# BalEv_ADC_v1_0.net
KiCad netlist of a schematic drawn in Altium Designer
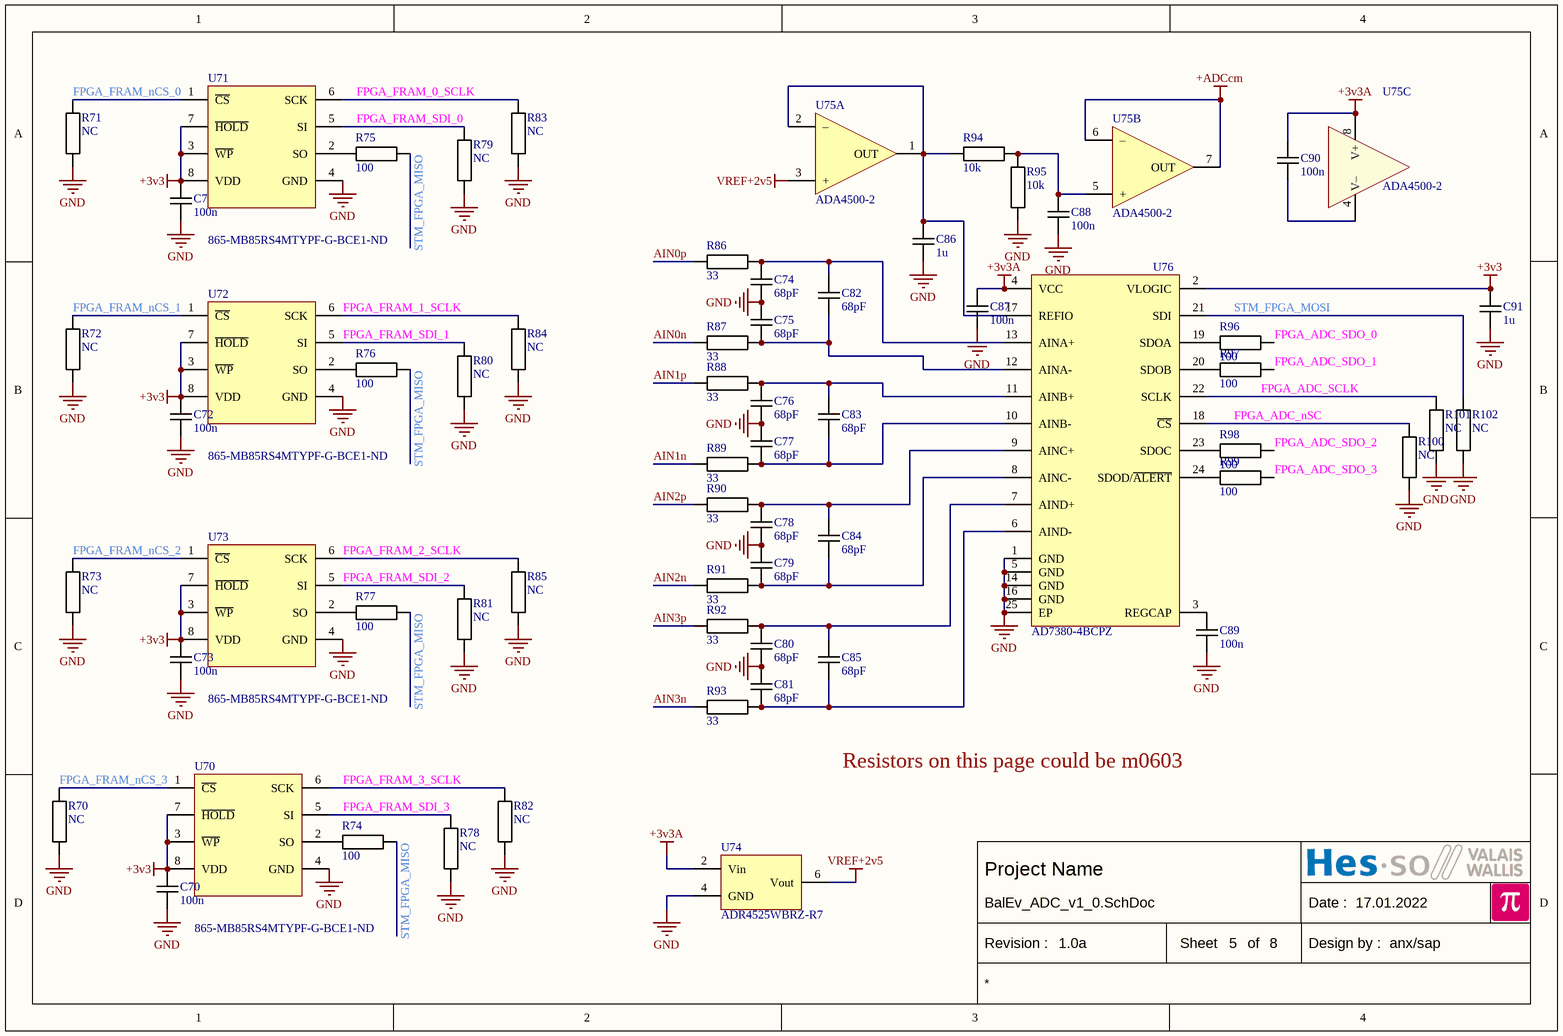
[diagram p0: BalEv_ADC_v1_0.SchDoc]

(export (version "E")
  (design (tool "Eeschema 10.0.6"))
  (components
    (comp (ref "C70")
      (value "100n")
      (footprint "CAPACITOR 1005 REFLOW")
      (description "Capacitor")
      (libsource (lib "Capacitor") (part "Capacitor"))
    )
    (comp (ref "C71")
      (value "100n")
      (footprint "CAPACITOR 1005 REFLOW")
      (description "Capacitor")
      (libsource (lib "Capacitor") (part "Capacitor"))
    )
    (comp (ref "C72")
      (value "100n")
      (footprint "CAPACITOR 1005 REFLOW")
      (description "Capacitor")
      (libsource (lib "Capacitor") (part "Capacitor"))
    )
    (comp (ref "C73")
      (value "100n")
      (footprint "CAPACITOR 1005 REFLOW")
      (description "Capacitor")
      (libsource (lib "Capacitor") (part "Capacitor"))
    )
    (comp (ref "C74")
      (value "68pF")
      (footprint "CAPACITOR 1005 REFLOW")
      (description "Capacitor")
      (libsource (lib "Capacitor") (part "Capacitor"))
    )
    (comp (ref "C75")
      (value "68pF")
      (footprint "CAPACITOR 1005 REFLOW")
      (description "Capacitor")
      (libsource (lib "Capacitor") (part "Capacitor"))
    )
    (comp (ref "C76")
      (value "68pF")
      (footprint "CAPACITOR 1005 REFLOW")
      (description "Capacitor")
      (libsource (lib "Capacitor") (part "Capacitor"))
    )
    (comp (ref "C77")
      (value "68pF")
      (footprint "CAPACITOR 1005 REFLOW")
      (description "Capacitor")
      (libsource (lib "Capacitor") (part "Capacitor"))
    )
    (comp (ref "C78")
      (value "68pF")
      (footprint "CAPACITOR 1005 REFLOW")
      (description "Capacitor")
      (libsource (lib "Capacitor") (part "Capacitor"))
    )
    (comp (ref "C79")
      (value "68pF")
      (footprint "CAPACITOR 1005 REFLOW")
      (description "Capacitor")
      (libsource (lib "Capacitor") (part "Capacitor"))
    )
    (comp (ref "C80")
      (value "68pF")
      (footprint "CAPACITOR 1005 REFLOW")
      (description "Capacitor")
      (libsource (lib "Capacitor") (part "Capacitor"))
    )
    (comp (ref "C81")
      (value "68pF")
      (footprint "CAPACITOR 1005 REFLOW")
      (description "Capacitor")
      (libsource (lib "Capacitor") (part "Capacitor"))
    )
    (comp (ref "C82")
      (value "68pF")
      (footprint "CAPACITOR 1005 REFLOW")
      (description "Capacitor")
      (libsource (lib "Capacitor") (part "Capacitor"))
    )
    (comp (ref "C83")
      (value "68pF")
      (footprint "CAPACITOR 1005 REFLOW")
      (description "Capacitor")
      (libsource (lib "Capacitor") (part "Capacitor"))
    )
    (comp (ref "C84")
      (value "68pF")
      (footprint "CAPACITOR 1005 REFLOW")
      (description "Capacitor")
      (libsource (lib "Capacitor") (part "Capacitor"))
    )
    (comp (ref "C85")
      (value "68pF")
      (footprint "CAPACITOR 1005 REFLOW")
      (description "Capacitor")
      (libsource (lib "Capacitor") (part "Capacitor"))
    )
    (comp (ref "C86")
      (value "1u")
      (footprint "CAPACITOR 1005 REFLOW")
      (description "Capacitor")
      (libsource (lib "Capacitor") (part "Capacitor"))
    )
    (comp (ref "C87")
      (value "100n")
      (footprint "CAPACITOR 1005 REFLOW")
      (description "Capacitor")
      (libsource (lib "Capacitor") (part "Capacitor"))
    )
    (comp (ref "C88")
      (value "100n")
      (footprint "CAPACITOR 1005 REFLOW")
      (description "Capacitor")
      (libsource (lib "Capacitor") (part "Capacitor"))
    )
    (comp (ref "C89")
      (value "100n")
      (footprint "CAPACITOR 1005 REFLOW")
      (description "Capacitor")
      (libsource (lib "Capacitor") (part "Capacitor"))
    )
    (comp (ref "C90")
      (value "100n")
      (footprint "CAPACITOR 1005 REFLOW")
      (description "Capacitor")
      (libsource (lib "Capacitor") (part "Capacitor"))
    )
    (comp (ref "C91")
      (value "1u")
      (footprint "CAPACITOR 1005 REFLOW")
      (description "Capacitor")
      (libsource (lib "Capacitor") (part "Capacitor"))
    )
    (comp (ref "R70")
      (value "NC")
      (footprint "RESISTOR 1005 REFLOW")
      (description "Resistor")
      (libsource (lib "Resistor") (part "Resistor"))
    )
    (comp (ref "R71")
      (value "NC")
      (footprint "RESISTOR 1005 REFLOW")
      (description "Resistor")
      (libsource (lib "Resistor") (part "Resistor"))
    )
    (comp (ref "R72")
      (value "NC")
      (footprint "RESISTOR 1005 REFLOW")
      (description "Resistor")
      (libsource (lib "Resistor") (part "Resistor"))
    )
    (comp (ref "R73")
      (value "NC")
      (footprint "RESISTOR 1005 REFLOW")
      (description "Resistor")
      (libsource (lib "Resistor") (part "Resistor"))
    )
    (comp (ref "R74")
      (value "100")
      (footprint "RESISTOR 1005 REFLOW")
      (description "Resistor")
      (libsource (lib "Resistor") (part "Resistor"))
    )
    (comp (ref "R75")
      (value "100")
      (footprint "RESISTOR 1005 REFLOW")
      (description "Resistor")
      (libsource (lib "Resistor") (part "Resistor"))
    )
    (comp (ref "R76")
      (value "100")
      (footprint "RESISTOR 1005 REFLOW")
      (description "Resistor")
      (libsource (lib "Resistor") (part "Resistor"))
    )
    (comp (ref "R77")
      (value "100")
      (footprint "RESISTOR 1005 REFLOW")
      (description "Resistor")
      (libsource (lib "Resistor") (part "Resistor"))
    )
    (comp (ref "R78")
      (value "NC")
      (footprint "RESISTOR 1005 REFLOW")
      (description "Resistor")
      (libsource (lib "Resistor") (part "Resistor"))
    )
    (comp (ref "R79")
      (value "NC")
      (footprint "RESISTOR 1005 REFLOW")
      (description "Resistor")
      (libsource (lib "Resistor") (part "Resistor"))
    )
    (comp (ref "R80")
      (value "NC")
      (footprint "RESISTOR 1005 REFLOW")
      (description "Resistor")
      (libsource (lib "Resistor") (part "Resistor"))
    )
    (comp (ref "R81")
      (value "NC")
      (footprint "RESISTOR 1005 REFLOW")
      (description "Resistor")
      (libsource (lib "Resistor") (part "Resistor"))
    )
    (comp (ref "R82")
      (value "NC")
      (footprint "RESISTOR 1005 REFLOW")
      (description "Resistor")
      (libsource (lib "Resistor") (part "Resistor"))
    )
    (comp (ref "R83")
      (value "NC")
      (footprint "RESISTOR 1005 REFLOW")
      (description "Resistor")
      (libsource (lib "Resistor") (part "Resistor"))
    )
    (comp (ref "R84")
      (value "NC")
      (footprint "RESISTOR 1005 REFLOW")
      (description "Resistor")
      (libsource (lib "Resistor") (part "Resistor"))
    )
    (comp (ref "R85")
      (value "NC")
      (footprint "RESISTOR 1005 REFLOW")
      (description "Resistor")
      (libsource (lib "Resistor") (part "Resistor"))
    )
    (comp (ref "R86")
      (value "33")
      (footprint "RESISTOR 1005 REFLOW")
      (description "Resistor")
      (libsource (lib "Resistor") (part "Resistor"))
    )
    (comp (ref "R87")
      (value "33")
      (footprint "RESISTOR 1005 REFLOW")
      (description "Resistor")
      (libsource (lib "Resistor") (part "Resistor"))
    )
    (comp (ref "R88")
      (value "33")
      (footprint "RESISTOR 1005 REFLOW")
      (description "Resistor")
      (libsource (lib "Resistor") (part "Resistor"))
    )
    (comp (ref "R89")
      (value "33")
      (footprint "RESISTOR 1005 REFLOW")
      (description "Resistor")
      (libsource (lib "Resistor") (part "Resistor"))
    )
    (comp (ref "R90")
      (value "33")
      (footprint "RESISTOR 1005 REFLOW")
      (description "Resistor")
      (libsource (lib "Resistor") (part "Resistor"))
    )
    (comp (ref "R91")
      (value "33")
      (footprint "RESISTOR 1005 REFLOW")
      (description "Resistor")
      (libsource (lib "Resistor") (part "Resistor"))
    )
    (comp (ref "R92")
      (value "33")
      (footprint "RESISTOR 1005 REFLOW")
      (description "Resistor")
      (libsource (lib "Resistor") (part "Resistor"))
    )
    (comp (ref "R93")
      (value "33")
      (footprint "RESISTOR 1005 REFLOW")
      (description "Resistor")
      (libsource (lib "Resistor") (part "Resistor"))
    )
    (comp (ref "R94")
      (value "10k")
      (footprint "RESISTOR 1005 REFLOW")
      (description "Resistor 0.01% (RNCF0603TKW10K0)")
      (libsource (lib "Resistor") (part "Resistor"))
    )
    (comp (ref "R95")
      (value "10k")
      (footprint "RESISTOR 1005 REFLOW")
      (description "Resistor 0.01% (RNCF0603TKW10K0)")
      (libsource (lib "Resistor") (part "Resistor"))
    )
    (comp (ref "R96")
      (value "100")
      (footprint "RESISTOR 1005 REFLOW")
      (description "Resistor")
      (libsource (lib "Resistor") (part "Resistor"))
    )
    (comp (ref "R97")
      (value "100")
      (footprint "RESISTOR 1005 REFLOW")
      (description "Resistor")
      (libsource (lib "Resistor") (part "Resistor"))
    )
    (comp (ref "R98")
      (value "100")
      (footprint "RESISTOR 1005 REFLOW")
      (description "Resistor")
      (libsource (lib "Resistor") (part "Resistor"))
    )
    (comp (ref "R99")
      (value "100")
      (footprint "RESISTOR 1005 REFLOW")
      (description "Resistor")
      (libsource (lib "Resistor") (part "Resistor"))
    )
    (comp (ref "R100")
      (value "NC")
      (footprint "RESISTOR 1005 REFLOW")
      (description "Resistor")
      (libsource (lib "Resistor") (part "Resistor"))
    )
    (comp (ref "R101")
      (value "NC")
      (footprint "RESISTOR 1005 REFLOW")
      (description "Resistor")
      (libsource (lib "Resistor") (part "Resistor"))
    )
    (comp (ref "R102")
      (value "NC")
      (footprint "RESISTOR 1005 REFLOW")
      (description "Resistor")
      (libsource (lib "Resistor") (part "Resistor"))
    )
    (comp (ref "U70")
      (value "865-MB85RS4MTYPF-G-BCE1-ND")
      (footprint "SO8W P1.27 C5.0X5.0 H2.0")
      (description "2-Mbit (256 K × 8) Serial (SPI) F-RAM")
      (libsource (lib "Memory") (part "FM25V20A-G"))
    )
    (comp (ref "U71")
      (value "865-MB85RS4MTYPF-G-BCE1-ND")
      (footprint "SO8W P1.27 C5.0X5.0 H2.0")
      (description "2-Mbit (256 K × 8) Serial (SPI) F-RAM")
      (libsource (lib "Memory") (part "FM25V20A-G"))
    )
    (comp (ref "U72")
      (value "865-MB85RS4MTYPF-G-BCE1-ND")
      (footprint "SO8W P1.27 C5.0X5.0 H2.0")
      (description "2-Mbit (256 K × 8) Serial (SPI) F-RAM")
      (libsource (lib "Memory") (part "FM25V20A-G"))
    )
    (comp (ref "U73")
      (value "865-MB85RS4MTYPF-G-BCE1-ND")
      (footprint "SO8W P1.27 C5.0X5.0 H2.0")
      (description "2-Mbit (256 K × 8) Serial (SPI) F-RAM")
      (libsource (lib "Memory") (part "FM25V20A-G"))
    )
    (comp (ref "U74")
      (value "ADR4525WBRZ-R7")
      (footprint "SO8 P1.27 C4.0X5.0 H1.75")
      (description "Ultralow Noise, High Accuracy Voltage References")
      (libsource (lib "Regulator") (part "ADR45___RZ (SOIC8)"))
    )
    (comp (ref "U75")
      (value "ADA4500-2")
      (footprint "MSOP8 P0.65 C3.0X3.0 H1.1")
      (description "Generic dual OPA 8 pins")
      (libsource (lib "Amplifier") (part "OPA DUAL"))
    )
    (comp (ref "U76")
      (value "AD7380-4BCPZ")
      (footprint "QFN24 P0.5 T0.5x0.5 C4.0x4.0 H0.6")
      (description "Differential Input, Quad, External Reference \r\nSimultaneous Sampling, 16-Bit, SAR ADC")
      (libsource (lib "Converter") (part "AD7380-4BCPZ"))
    )
  )
  (nets
    (net (code "1") (name "+3v3") (class "Default")
      (node (ref "C70") (pin "2") (pinfunction "2_2") (pintype "passive"))
      (node (ref "C71") (pin "2") (pinfunction "2_2") (pintype "passive"))
      (node (ref "C72") (pin "2") (pinfunction "2_2") (pintype "passive"))
      (node (ref "C73") (pin "2") (pinfunction "2_2") (pintype "passive"))
      (node (ref "C91") (pin "2") (pinfunction "2_2") (pintype "passive"))
      (node (ref "U70") (pin "3") (pinfunction "~{WP}_3") (pintype "passive"))
      (node (ref "U70") (pin "7") (pinfunction "~{HOLD}_7") (pintype "passive"))
      (node (ref "U70") (pin "8") (pinfunction "VDD_8") (pintype "power_in"))
      (node (ref "U71") (pin "3") (pinfunction "~{WP}_3") (pintype "passive"))
      (node (ref "U71") (pin "7") (pinfunction "~{HOLD}_7") (pintype "passive"))
      (node (ref "U71") (pin "8") (pinfunction "VDD_8") (pintype "power_in"))
      (node (ref "U72") (pin "3") (pinfunction "~{WP}_3") (pintype "passive"))
      (node (ref "U72") (pin "7") (pinfunction "~{HOLD}_7") (pintype "passive"))
      (node (ref "U72") (pin "8") (pinfunction "VDD_8") (pintype "power_in"))
      (node (ref "U73") (pin "3") (pinfunction "~{WP}_3") (pintype "passive"))
      (node (ref "U73") (pin "7") (pinfunction "~{HOLD}_7") (pintype "passive"))
      (node (ref "U73") (pin "8") (pinfunction "VDD_8") (pintype "power_in"))
      (node (ref "U76") (pin "2") (pinfunction "VLOGIC_2") (pintype "passive"))
    )
    (net (code "2") (name "+3v3A") (class "Default")
      (node (ref "C87") (pin "2") (pinfunction "2_2") (pintype "passive"))
      (node (ref "C90") (pin "2") (pinfunction "2_2") (pintype "passive"))
      (node (ref "U74") (pin "2") (pinfunction "Vin_2") (pintype "passive"))
      (node (ref "U75") (pin "8") (pinfunction "V+_8") (pintype "passive"))
      (node (ref "U76") (pin "4") (pinfunction "VCC_4") (pintype "passive"))
    )
    (net (code "3") (name "+ADCcm") (class "Default")
      (node (ref "U75") (pin "6") (pinfunction "–_6") (pintype "passive"))
      (node (ref "U75") (pin "7") (pinfunction "OUT_7") (pintype "passive"))
    )
    (net (code "4") (name "/AIN0n") (class "Default")
      (node (ref "R87") (pin "1") (pinfunction "1_1") (pintype "passive"))
    )
    (net (code "5") (name "/AIN0p") (class "Default")
      (node (ref "R86") (pin "1") (pinfunction "1_1") (pintype "passive"))
    )
    (net (code "6") (name "/AIN1n") (class "Default")
      (node (ref "R89") (pin "1") (pinfunction "1_1") (pintype "passive"))
    )
    (net (code "7") (name "/AIN1p") (class "Default")
      (node (ref "R88") (pin "1") (pinfunction "1_1") (pintype "passive"))
    )
    (net (code "8") (name "/AIN2n") (class "Default")
      (node (ref "R91") (pin "1") (pinfunction "1_1") (pintype "passive"))
    )
    (net (code "9") (name "/AIN2p") (class "Default")
      (node (ref "R90") (pin "1") (pinfunction "1_1") (pintype "passive"))
    )
    (net (code "10") (name "/AIN3n") (class "Default")
      (node (ref "R93") (pin "1") (pinfunction "1_1") (pintype "passive"))
    )
    (net (code "11") (name "/AIN3p") (class "Default")
      (node (ref "R92") (pin "1") (pinfunction "1_1") (pintype "passive"))
    )
    (net (code "12") (name "/FPGA_ADC_SCLK") (class "Default")
      (node (ref "R101") (pin "2") (pinfunction "2_2") (pintype "passive"))
      (node (ref "U76") (pin "22") (pinfunction "SCLK_22") (pintype "passive"))
    )
    (net (code "13") (name "/FPGA_ADC_SDO_0") (class "Default")
      (node (ref "R96") (pin "2") (pinfunction "2_2") (pintype "passive"))
    )
    (net (code "14") (name "/FPGA_ADC_SDO_1") (class "Default")
      (node (ref "R97") (pin "2") (pinfunction "2_2") (pintype "passive"))
    )
    (net (code "15") (name "/FPGA_ADC_SDO_2") (class "Default")
      (node (ref "R98") (pin "2") (pinfunction "2_2") (pintype "passive"))
    )
    (net (code "16") (name "/FPGA_ADC_SDO_3") (class "Default")
      (node (ref "R99") (pin "2") (pinfunction "2_2") (pintype "passive"))
    )
    (net (code "17") (name "/FPGA_ADC_nSC") (class "Default")
      (node (ref "R100") (pin "2") (pinfunction "2_2") (pintype "passive"))
      (node (ref "U76") (pin "18") (pinfunction "~{CS}_18") (pintype "passive"))
    )
    (net (code "18") (name "/FPGA_FRAM_0_SCLK") (class "Default")
      (node (ref "R83") (pin "2") (pinfunction "2_2") (pintype "passive"))
      (node (ref "U71") (pin "6") (pinfunction "SCK_6") (pintype "passive"))
    )
    (net (code "19") (name "/FPGA_FRAM_1_SCLK") (class "Default")
      (node (ref "R84") (pin "2") (pinfunction "2_2") (pintype "passive"))
      (node (ref "U72") (pin "6") (pinfunction "SCK_6") (pintype "passive"))
    )
    (net (code "20") (name "/FPGA_FRAM_2_SCLK") (class "Default")
      (node (ref "R85") (pin "2") (pinfunction "2_2") (pintype "passive"))
      (node (ref "U73") (pin "6") (pinfunction "SCK_6") (pintype "passive"))
    )
    (net (code "21") (name "/FPGA_FRAM_3_SCLK") (class "Default")
      (node (ref "R82") (pin "2") (pinfunction "2_2") (pintype "passive"))
      (node (ref "U70") (pin "6") (pinfunction "SCK_6") (pintype "passive"))
    )
    (net (code "22") (name "/FPGA_FRAM_SDI_0") (class "Default")
      (node (ref "R79") (pin "2") (pinfunction "2_2") (pintype "passive"))
      (node (ref "U71") (pin "5") (pinfunction "SI_5") (pintype "passive"))
    )
    (net (code "23") (name "/FPGA_FRAM_SDI_1") (class "Default")
      (node (ref "R80") (pin "2") (pinfunction "2_2") (pintype "passive"))
      (node (ref "U72") (pin "5") (pinfunction "SI_5") (pintype "passive"))
    )
    (net (code "24") (name "/FPGA_FRAM_SDI_2") (class "Default")
      (node (ref "R81") (pin "2") (pinfunction "2_2") (pintype "passive"))
      (node (ref "U73") (pin "5") (pinfunction "SI_5") (pintype "passive"))
    )
    (net (code "25") (name "/FPGA_FRAM_SDI_3") (class "Default")
      (node (ref "R78") (pin "2") (pinfunction "2_2") (pintype "passive"))
      (node (ref "U70") (pin "5") (pinfunction "SI_5") (pintype "passive"))
    )
    (net (code "26") (name "/FPGA_FRAM_nCS_0") (class "Default")
      (node (ref "R71") (pin "2") (pinfunction "2_2") (pintype "passive"))
      (node (ref "U71") (pin "1") (pinfunction "~{CS}_1") (pintype "passive"))
    )
    (net (code "27") (name "/FPGA_FRAM_nCS_1") (class "Default")
      (node (ref "R72") (pin "2") (pinfunction "2_2") (pintype "passive"))
      (node (ref "U72") (pin "1") (pinfunction "~{CS}_1") (pintype "passive"))
    )
    (net (code "28") (name "/FPGA_FRAM_nCS_2") (class "Default")
      (node (ref "R73") (pin "2") (pinfunction "2_2") (pintype "passive"))
      (node (ref "U73") (pin "1") (pinfunction "~{CS}_1") (pintype "passive"))
    )
    (net (code "29") (name "/FPGA_FRAM_nCS_3") (class "Default")
      (node (ref "R70") (pin "2") (pinfunction "2_2") (pintype "passive"))
      (node (ref "U70") (pin "1") (pinfunction "~{CS}_1") (pintype "passive"))
    )
    (net (code "30") (name "/STM_FPGA_MISO") (class "Default")
      (node (ref "R74") (pin "2") (pinfunction "2_2") (pintype "passive"))
      (node (ref "R75") (pin "2") (pinfunction "2_2") (pintype "passive"))
      (node (ref "R76") (pin "2") (pinfunction "2_2") (pintype "passive"))
      (node (ref "R77") (pin "2") (pinfunction "2_2") (pintype "passive"))
    )
    (net (code "31") (name "/STM_FPGA_MOSI") (class "Default")
      (node (ref "R102") (pin "2") (pinfunction "2_2") (pintype "passive"))
      (node (ref "U76") (pin "21") (pinfunction "SDI_21") (pintype "passive"))
    )
    (net (code "32") (name "GND") (class "Default")
      (node (ref "C70") (pin "1") (pinfunction "1_1") (pintype "passive"))
      (node (ref "C71") (pin "1") (pinfunction "1_1") (pintype "passive"))
      (node (ref "C72") (pin "1") (pinfunction "1_1") (pintype "passive"))
      (node (ref "C73") (pin "1") (pinfunction "1_1") (pintype "passive"))
      (node (ref "C74") (pin "2") (pinfunction "2_2") (pintype "passive"))
      (node (ref "C75") (pin "1") (pinfunction "1_1") (pintype "passive"))
      (node (ref "C76") (pin "2") (pinfunction "2_2") (pintype "passive"))
      (node (ref "C77") (pin "1") (pinfunction "1_1") (pintype "passive"))
      (node (ref "C78") (pin "2") (pinfunction "2_2") (pintype "passive"))
      (node (ref "C79") (pin "1") (pinfunction "1_1") (pintype "passive"))
      (node (ref "C80") (pin "2") (pinfunction "2_2") (pintype "passive"))
      (node (ref "C81") (pin "1") (pinfunction "1_1") (pintype "passive"))
      (node (ref "C86") (pin "1") (pinfunction "1_1") (pintype "passive"))
      (node (ref "C87") (pin "1") (pinfunction "1_1") (pintype "passive"))
      (node (ref "C88") (pin "1") (pinfunction "1_1") (pintype "passive"))
      (node (ref "C89") (pin "1") (pinfunction "1_1") (pintype "passive"))
      (node (ref "C91") (pin "1") (pinfunction "1_1") (pintype "passive"))
      (node (ref "R100") (pin "1") (pinfunction "1_1") (pintype "passive"))
      (node (ref "R101") (pin "1") (pinfunction "1_1") (pintype "passive"))
      (node (ref "R102") (pin "1") (pinfunction "1_1") (pintype "passive"))
      (node (ref "R70") (pin "1") (pinfunction "1_1") (pintype "passive"))
      (node (ref "R71") (pin "1") (pinfunction "1_1") (pintype "passive"))
      (node (ref "R72") (pin "1") (pinfunction "1_1") (pintype "passive"))
      (node (ref "R73") (pin "1") (pinfunction "1_1") (pintype "passive"))
      (node (ref "R78") (pin "1") (pinfunction "1_1") (pintype "passive"))
      (node (ref "R79") (pin "1") (pinfunction "1_1") (pintype "passive"))
      (node (ref "R80") (pin "1") (pinfunction "1_1") (pintype "passive"))
      (node (ref "R81") (pin "1") (pinfunction "1_1") (pintype "passive"))
      (node (ref "R82") (pin "1") (pinfunction "1_1") (pintype "passive"))
      (node (ref "R83") (pin "1") (pinfunction "1_1") (pintype "passive"))
      (node (ref "R84") (pin "1") (pinfunction "1_1") (pintype "passive"))
      (node (ref "R85") (pin "1") (pinfunction "1_1") (pintype "passive"))
      (node (ref "R95") (pin "1") (pinfunction "1_1") (pintype "passive"))
      (node (ref "U70") (pin "4") (pinfunction "GND_4") (pintype "power_in"))
      (node (ref "U71") (pin "4") (pinfunction "GND_4") (pintype "power_in"))
      (node (ref "U72") (pin "4") (pinfunction "GND_4") (pintype "power_in"))
      (node (ref "U73") (pin "4") (pinfunction "GND_4") (pintype "power_in"))
      (node (ref "U74") (pin "4") (pinfunction "GND_4") (pintype "passive"))
      (node (ref "U76") (pin "1") (pinfunction "GND_1") (pintype "passive"))
      (node (ref "U76") (pin "14") (pinfunction "GND_14") (pintype "passive"))
      (node (ref "U76") (pin "16") (pinfunction "GND_16") (pintype "passive"))
      (node (ref "U76") (pin "25") (pinfunction "EP_25") (pintype "passive"))
      (node (ref "U76") (pin "5") (pinfunction "GND_5") (pintype "passive"))
    )
    (net (code "33") (name "Net-(U70-SO)") (class "Default")
      (node (ref "R74") (pin "1") (pinfunction "1_1") (pintype "passive"))
      (node (ref "U70") (pin "2") (pinfunction "SO_2") (pintype "passive"))
    )
    (net (code "34") (name "Net-(U71-SO)") (class "Default")
      (node (ref "R75") (pin "1") (pinfunction "1_1") (pintype "passive"))
      (node (ref "U71") (pin "2") (pinfunction "SO_2") (pintype "passive"))
    )
    (net (code "35") (name "Net-(U72-SO)") (class "Default")
      (node (ref "R76") (pin "1") (pinfunction "1_1") (pintype "passive"))
      (node (ref "U72") (pin "2") (pinfunction "SO_2") (pintype "passive"))
    )
    (net (code "36") (name "Net-(U73-SO)") (class "Default")
      (node (ref "R77") (pin "1") (pinfunction "1_1") (pintype "passive"))
      (node (ref "U73") (pin "2") (pinfunction "SO_2") (pintype "passive"))
    )
    (net (code "37") (name "Net-(U75A-OUT)") (class "Default")
      (node (ref "C86") (pin "2") (pinfunction "2_2") (pintype "passive"))
      (node (ref "R94") (pin "1") (pinfunction "1_1") (pintype "passive"))
      (node (ref "U75") (pin "1") (pinfunction "OUT_1") (pintype "passive"))
      (node (ref "U75") (pin "2") (pinfunction "–_2") (pintype "passive"))
      (node (ref "U76") (pin "17") (pinfunction "REFIO_17") (pintype "passive"))
    )
    (net (code "38") (name "Net-(U75B-+)") (class "Default")
      (node (ref "C88") (pin "2") (pinfunction "2_2") (pintype "passive"))
      (node (ref "R94") (pin "2") (pinfunction "2_2") (pintype "passive"))
      (node (ref "R95") (pin "2") (pinfunction "2_2") (pintype "passive"))
      (node (ref "U75") (pin "5") (pinfunction "+_5") (pintype "passive"))
    )
    (net (code "39") (name "Net-(U75C-V–)") (class "Default")
      (node (ref "C90") (pin "1") (pinfunction "1_1") (pintype "passive"))
      (node (ref "U75") (pin "4") (pinfunction "V–_4") (pintype "passive"))
    )
    (net (code "40") (name "Net-(U76-AINA+)") (class "Default")
      (node (ref "C74") (pin "1") (pinfunction "1_1") (pintype "passive"))
      (node (ref "C82") (pin "2") (pinfunction "2_2") (pintype "passive"))
      (node (ref "R86") (pin "2") (pinfunction "2_2") (pintype "passive"))
      (node (ref "U76") (pin "13") (pinfunction "AINA+_13") (pintype "passive"))
    )
    (net (code "41") (name "Net-(U76-AINA-)") (class "Default")
      (node (ref "C75") (pin "2") (pinfunction "2_2") (pintype "passive"))
      (node (ref "C82") (pin "1") (pinfunction "1_1") (pintype "passive"))
      (node (ref "R87") (pin "2") (pinfunction "2_2") (pintype "passive"))
      (node (ref "U76") (pin "12") (pinfunction "AINA-_12") (pintype "passive"))
    )
    (net (code "42") (name "Net-(U76-AINB+)") (class "Default")
      (node (ref "C76") (pin "1") (pinfunction "1_1") (pintype "passive"))
      (node (ref "C83") (pin "2") (pinfunction "2_2") (pintype "passive"))
      (node (ref "R88") (pin "2") (pinfunction "2_2") (pintype "passive"))
      (node (ref "U76") (pin "11") (pinfunction "AINB+_11") (pintype "passive"))
    )
    (net (code "43") (name "Net-(U76-AINB-)") (class "Default")
      (node (ref "C77") (pin "2") (pinfunction "2_2") (pintype "passive"))
      (node (ref "C83") (pin "1") (pinfunction "1_1") (pintype "passive"))
      (node (ref "R89") (pin "2") (pinfunction "2_2") (pintype "passive"))
      (node (ref "U76") (pin "10") (pinfunction "AINB-_10") (pintype "passive"))
    )
    (net (code "44") (name "Net-(U76-AINC+)") (class "Default")
      (node (ref "C78") (pin "1") (pinfunction "1_1") (pintype "passive"))
      (node (ref "C84") (pin "2") (pinfunction "2_2") (pintype "passive"))
      (node (ref "R90") (pin "2") (pinfunction "2_2") (pintype "passive"))
      (node (ref "U76") (pin "9") (pinfunction "AINC+_9") (pintype "passive"))
    )
    (net (code "45") (name "Net-(U76-AINC-)") (class "Default")
      (node (ref "C79") (pin "2") (pinfunction "2_2") (pintype "passive"))
      (node (ref "C84") (pin "1") (pinfunction "1_1") (pintype "passive"))
      (node (ref "R91") (pin "2") (pinfunction "2_2") (pintype "passive"))
      (node (ref "U76") (pin "8") (pinfunction "AINC-_8") (pintype "passive"))
    )
    (net (code "46") (name "Net-(U76-AIND+)") (class "Default")
      (node (ref "C80") (pin "1") (pinfunction "1_1") (pintype "passive"))
      (node (ref "C85") (pin "2") (pinfunction "2_2") (pintype "passive"))
      (node (ref "R92") (pin "2") (pinfunction "2_2") (pintype "passive"))
      (node (ref "U76") (pin "7") (pinfunction "AIND+_7") (pintype "passive"))
    )
    (net (code "47") (name "Net-(U76-AIND-)") (class "Default")
      (node (ref "C81") (pin "2") (pinfunction "2_2") (pintype "passive"))
      (node (ref "C85") (pin "1") (pinfunction "1_1") (pintype "passive"))
      (node (ref "R93") (pin "2") (pinfunction "2_2") (pintype "passive"))
      (node (ref "U76") (pin "6") (pinfunction "AIND-_6") (pintype "passive"))
    )
    (net (code "48") (name "Net-(U76-REGCAP)") (class "Default")
      (node (ref "C89") (pin "2") (pinfunction "2_2") (pintype "passive"))
      (node (ref "U76") (pin "3") (pinfunction "REGCAP_3") (pintype "passive"))
    )
    (net (code "49") (name "Net-(U76-SDOA)") (class "Default")
      (node (ref "R96") (pin "1") (pinfunction "1_1") (pintype "passive"))
      (node (ref "U76") (pin "19") (pinfunction "SDOA_19") (pintype "passive"))
    )
    (net (code "50") (name "Net-(U76-SDOB)") (class "Default")
      (node (ref "R97") (pin "1") (pinfunction "1_1") (pintype "passive"))
      (node (ref "U76") (pin "20") (pinfunction "SDOB_20") (pintype "passive"))
    )
    (net (code "51") (name "Net-(U76-SDOC)") (class "Default")
      (node (ref "R98") (pin "1") (pinfunction "1_1") (pintype "passive"))
      (node (ref "U76") (pin "23") (pinfunction "SDOC_23") (pintype "passive"))
    )
    (net (code "52") (name "Net-(U76-SDOD{slash}~{ALERT})") (class "Default")
      (node (ref "R99") (pin "1") (pinfunction "1_1") (pintype "passive"))
      (node (ref "U76") (pin "24") (pinfunction "SDOD/~{ALERT}_24") (pintype "passive"))
    )
    (net (code "53") (name "VREF+2v5") (class "Default")
      (node (ref "U74") (pin "6") (pinfunction "Vout_6") (pintype "passive"))
      (node (ref "U75") (pin "3") (pinfunction "+_3") (pintype "passive"))
    )
  )
)
